# PAPI_M3_RF.net
KiCad netlist of a schematic drawn in Altium Designer
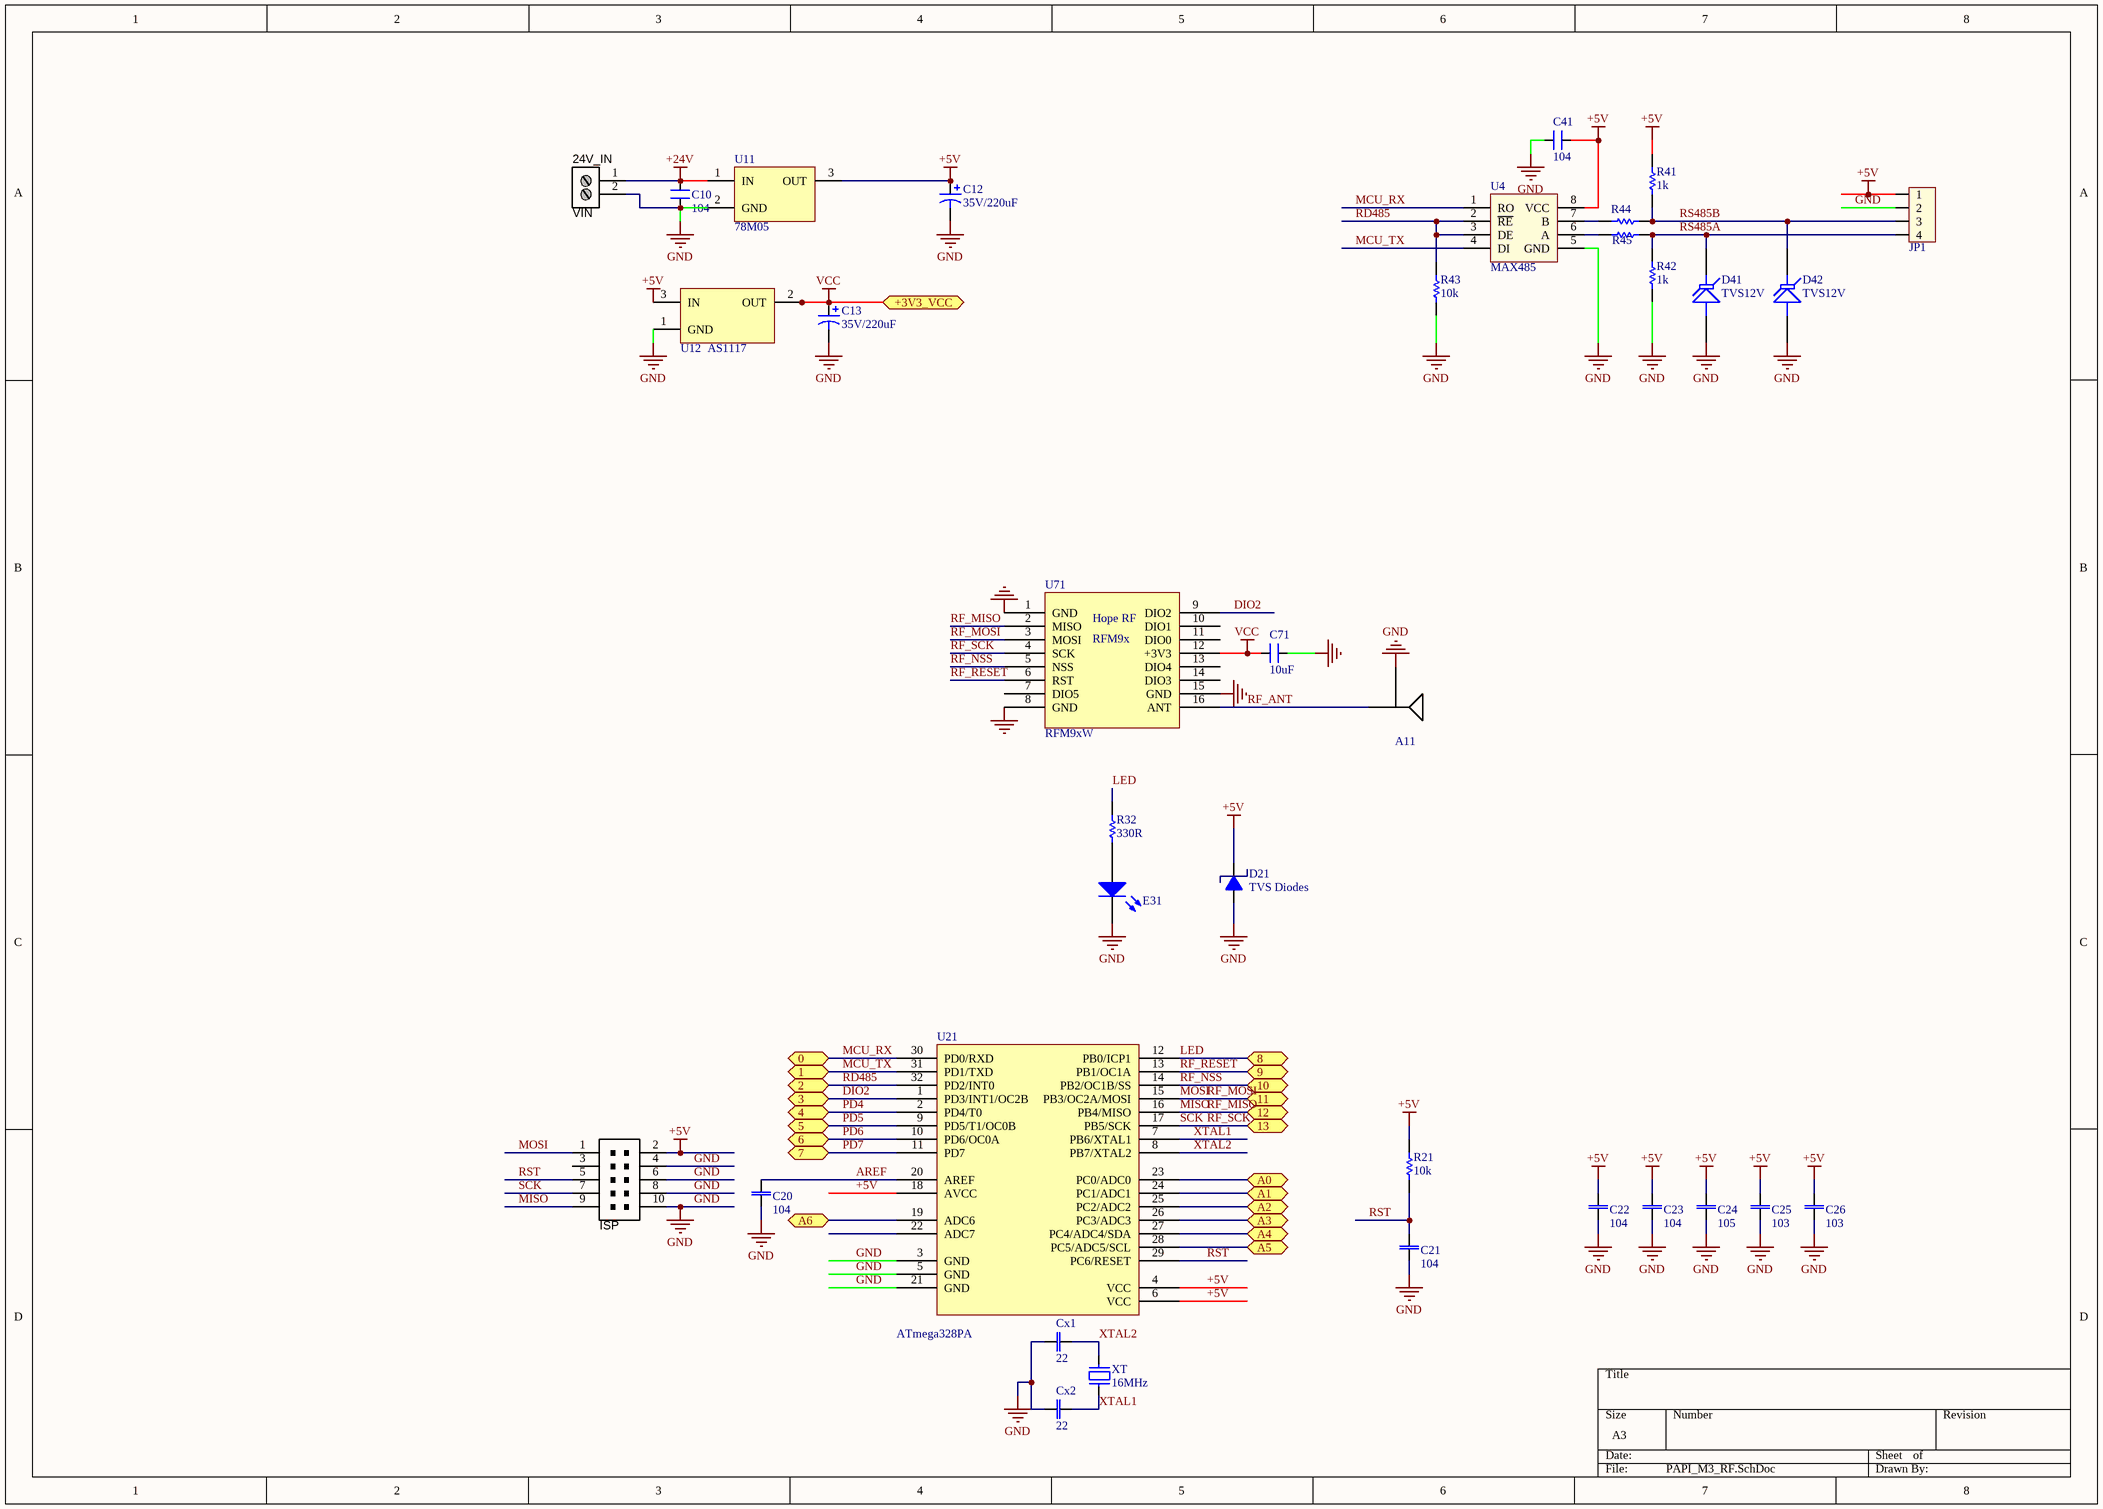
[diagram p0: PAPI_M3_RF.SchDoc]

(export (version "E")
  (design (tool "Eeschema 10.0.6"))
  (components
    (comp (ref "24V_IN")
      (value "VIN")
      (footprint "2P_PCB1")
      (description "Terminal Block Screw Type THT 2-Position 3.81mm pitch")
      (libsource (lib "PBL - Connectors") (part "2P_ScrewTerm_90S_3.81MM"))
    )
    (comp (ref "A11") (value "Giắc anten SMA") (footprint "SMA") (libsource (lib "Tuan") (part "RF_SMA")))
    (comp (ref "C10")
      (value "104")
      (footprint "CAPC2012N_F")
      (fields (field (name "Comment") "Cap_104_0603"))
      (libsource (lib "") (part "CAP NP_1"))
    )
    (comp (ref "C12")
      (value "35V/220uF")
      (footprint "CAPE3.5-5.0MM_Rad_10x14mm")
      (fields (field (name "Comment") "Cap"))
      (libsource (lib "Tuan") (part "Cap"))
    )
    (comp (ref "C13")
      (value "35V/220uF")
      (footprint "CAPE3.5-5.0MM_Rad_10x14mm")
      (fields (field (name "Comment") "Cap"))
      (libsource (lib "Tuan") (part "Cap"))
    )
    (comp (ref "C20")
      (value "104")
      (footprint "PBL - SMD Packages:CAPC2012N_F")
      (description "Capacitor non polarized")
      (fields (field (name "Comment") "Tụ điện dán 0603104"))
      (libsource (lib "Tuan") (part "CAP NP"))
    )
    (comp (ref "C21")
      (value "104")
      (footprint "PBL - SMD Packages:CAPC2012N_F")
      (description "Capacitor non polarized")
      (fields (field (name "Comment") "Tụ điện dán 0603104"))
      (libsource (lib "Tuan") (part "CAP NP"))
    )
    (comp (ref "C22")
      (value "104")
      (footprint "PBL - SMD Packages:CAPC2012N_F")
      (description "Capacitor non polarized")
      (fields (field (name "Comment") "Tụ điện dán 0805104"))
      (libsource (lib "Tuan") (part "CAP NP"))
    )
    (comp (ref "C23")
      (value "104")
      (footprint "PBL - SMD Packages:CAPC2012N_F")
      (description "Capacitor non polarized")
      (fields (field (name "Comment") "Tụ điện dán 0805104"))
      (libsource (lib "Tuan") (part "CAP NP"))
    )
    (comp (ref "C24")
      (value "105")
      (footprint "PBL - SMD Packages:CAPC2012N_F")
      (description "Capacitor non polarized")
      (fields (field (name "Comment") "Tụ điện dán 0805105"))
      (libsource (lib "Tuan") (part "CAP NP"))
    )
    (comp (ref "C25")
      (value "103")
      (footprint "PBL - SMD Packages:CAPC2012N_F")
      (description "Capacitor non polarized")
      (fields (field (name "Comment") "Tụ điện dán 0805103"))
      (libsource (lib "Tuan") (part "CAP NP"))
    )
    (comp (ref "C26")
      (value "103")
      (footprint "PBL - SMD Packages:CAPC2012N_F")
      (description "Capacitor non polarized")
      (fields (field (name "Comment") "Tụ điện dán 0805103"))
      (libsource (lib "Tuan") (part "CAP NP"))
    )
    (comp (ref "C41")
      (value "104")
      (footprint "CAPC2012N_F")
      (fields (field (name "Comment") "Cap_104_0603"))
      (libsource (lib "") (part "CAP NP_1"))
    )
    (comp (ref "C71")
      (value "10uF")
      (footprint "CAPC2012N_F")
      (fields (field (name "Comment") "Cap_10uF_0805"))
      (libsource (lib "") (part "CAP NP_1"))
    )
    (comp (ref "Cx1")
      (value "22")
      (footprint "PBL - SMD Packages:CAPC2012N_F")
      (description "Capacitor non polarized")
      (fields (field (name "Comment") "Tụ điện dán 060322"))
      (libsource (lib "Tuan") (part "CAP NP"))
    )
    (comp (ref "Cx2")
      (value "22")
      (footprint "PBL - SMD Packages:CAPC2012N_F")
      (description "Capacitor non polarized")
      (fields (field (name "Comment") "Tụ điện dán 060322"))
      (libsource (lib "Tuan") (part "CAP NP"))
    )
    (comp (ref "D21")
      (value "TVS Diodes")
      (footprint "DO-214AC")
      (description "TVS Diodes - Transient Voltage Suppressors")
      (libsource (lib "Tuan") (part "TVS Diodes"))
    )
    (comp (ref "D41")
      (value "TVS12V")
      (footprint "DO-214AA")
      (description "Transient Voltage Suppression (TVS) Diode")
      (fields (field (name "PUBLISHER") "Altium Limited"))
      (libsource (lib "Miscellaneous Devices") (part "Tranzorb"))
    )
    (comp (ref "D42")
      (value "TVS12V")
      (footprint "DO-214AA")
      (description "Transient Voltage Suppression (TVS) Diode")
      (fields (field (name "PUBLISHER") "Altium Limited"))
      (libsource (lib "Miscellaneous Devices") (part "Tranzorb"))
    )
    (comp (ref "E31") (value "Led") (footprint "LED 5mm Green") (libsource (lib "Tuan") (part "Led")))
    (comp (ref "ISP")
      (value "Giắc đôi 5x2 chân 2.54mm")
      (footprint "10P_PCB_HEADER_BRD_MNT")
      (description "Header THD 10 POS Double-row 2.54mm pitch")
      (libsource (lib "PBL - Connectors") (part "CONN_HEADER_2x5P_0.100in_Male"))
    )
    (comp (ref "JP1")
      (value "JP4")
      (footprint "heromap:CON4")
      (description "Connector 4")
      (libsource (lib "heromap") (part "Con4"))
    )
    (comp (ref "R21")
      (value "10k")
      (footprint "PBL - SMD Packages:RESC2012N_F")
      (description "Resistor")
      (fields (field (name "Comment") "Điện trở dán 060310k"))
      (libsource (lib "Tuan") (part "Res"))
    )
    (comp (ref "R32")
      (value "330R")
      (footprint "PBL - SMD Packages:RESC2012N_F")
      (description "Resistor")
      (fields (field (name "Comment") "Điện trở dán 0603330R"))
      (libsource (lib "Tuan") (part "Res"))
    )
    (comp (ref "R41")
      (value "1k")
      (footprint "RESC2012N_F")
      (fields (field (name "Comment") "Res_1k_0603"))
      (libsource (lib "Tuan") (part "Res"))
    )
    (comp (ref "R42")
      (value "1k")
      (footprint "RESC2012N_F")
      (fields (field (name "Comment") "Res_1k_0603"))
      (libsource (lib "Tuan") (part "Res"))
    )
    (comp (ref "R43")
      (value "10k")
      (footprint "RESC2012N_F")
      (fields (field (name "Comment") "Res_10k_0603"))
      (libsource (lib "Tuan") (part "Res"))
    )
    (comp (ref "R44") (value "Res_10R_0805") (footprint "RESC2012N_F") (libsource (lib "Tuan") (part "Res")))
    (comp (ref "R45") (value "Res_10R_0805") (footprint "RESC2012N_F") (libsource (lib "Tuan") (part "Res")))
    (comp (ref "U4")
      (value "MAX485")
      (footprint "SOIC 8")
      (description "RS232 - RS485 (Same sn75176)")
      (libsource (lib "heromap") (part "MAX485"))
    )
    (comp (ref "U11") (value "78M05") (footprint "TO252 D-PAK") (libsource (lib "Tuan") (part "LM78xx")))
    (comp (ref "U12") (value "AS1117") (footprint "SOT223-4N") (libsource (lib "Tuan") (part "AS1117")))
    (comp (ref "U21")
      (value "ATmega328PA")
      (footprint "TQFP32")
      (description "ATmega48/168/328")
      (libsource (lib "Tuan") (part "ATmega48/168/328"))
    )
    (comp (ref "U71") (value "RFM9xW") (footprint "RFM9xW") (libsource (lib "Tuan") (part "RFM9xW")))
    (comp (ref "XT") (value "16MHz") (footprint "XT2") (libsource (lib "Tuan") (part "Crystal")))
  )
  (nets
    (net (code "1") (name "+5V") (class "Default")
      (node (ref "C12") (pin "1") (pinfunction "1_1") (pintype "passive"))
      (node (ref "C22") (pin "2") (pinfunction "2_2") (pintype "passive"))
      (node (ref "C23") (pin "2") (pinfunction "2_2") (pintype "passive"))
      (node (ref "C24") (pin "2") (pinfunction "2_2") (pintype "passive"))
      (node (ref "C25") (pin "2") (pinfunction "2_2") (pintype "passive"))
      (node (ref "C26") (pin "2") (pinfunction "2_2") (pintype "passive"))
      (node (ref "C41") (pin "1") (pinfunction "1_1") (pintype "passive"))
      (node (ref "D21") (pin "K") (pinfunction "K_K") (pintype "passive"))
      (node (ref "ISP") (pin "2") (pinfunction "2_2") (pintype "passive"))
      (node (ref "JP1") (pin "1") (pinfunction "1_1") (pintype "passive"))
      (node (ref "R21") (pin "2") (pinfunction "2_2") (pintype "passive"))
      (node (ref "R41") (pin "2") (pinfunction "2_2") (pintype "passive"))
      (node (ref "U11") (pin "3") (pinfunction "OUT_3") (pintype "passive"))
      (node (ref "U12") (pin "3") (pinfunction "IN_3") (pintype "power_in"))
      (node (ref "U21") (pin "18") (pinfunction "AVCC_18") (pintype "passive"))
      (node (ref "U21") (pin "4") (pinfunction "VCC_4") (pintype "passive"))
      (node (ref "U21") (pin "6") (pinfunction "VCC_6") (pintype "passive"))
      (node (ref "U4") (pin "8") (pinfunction "VCC_8") (pintype "passive"))
    )
    (net (code "2") (name "+24V") (class "Default")
      (node (ref "24V_IN") (pin "1") (pinfunction "1_1") (pintype "passive"))
      (node (ref "C10") (pin "2") (pinfunction "2_2") (pintype "passive"))
      (node (ref "U11") (pin "1") (pinfunction "IN_1") (pintype "passive"))
    )
    (net (code "3") (name "/A0") (class "Default")
      (node (ref "U21") (pin "23") (pinfunction "PC0/ADC0_23") (pintype "passive"))
    )
    (net (code "4") (name "/A1") (class "Default")
      (node (ref "U21") (pin "24") (pinfunction "PC1/ADC1_24") (pintype "passive"))
    )
    (net (code "5") (name "/A2") (class "Default")
      (node (ref "U21") (pin "25") (pinfunction "PC2/ADC2_25") (pintype "passive"))
    )
    (net (code "6") (name "/A3") (class "Default")
      (node (ref "U21") (pin "26") (pinfunction "PC3/ADC3_26") (pintype "passive"))
    )
    (net (code "7") (name "/A4") (class "Default")
      (node (ref "U21") (pin "27") (pinfunction "PC4/ADC4/SDA_27") (pintype "passive"))
    )
    (net (code "8") (name "/A5") (class "Default")
      (node (ref "U21") (pin "28") (pinfunction "PC5/ADC5/SCL_28") (pintype "passive"))
    )
    (net (code "9") (name "/A6") (class "Default")
      (node (ref "U21") (pin "19") (pinfunction "ADC6_19") (pintype "passive"))
    )
    (net (code "10") (name "/AREF") (class "Default")
      (node (ref "C20") (pin "2") (pinfunction "2_2") (pintype "passive"))
      (node (ref "U21") (pin "20") (pinfunction "AREF_20") (pintype "passive"))
    )
    (net (code "11") (name "/DIO2") (class "Default")
      (node (ref "U21") (pin "1") (pinfunction "PD3/INT1/OC2B_1") (pintype "passive"))
      (node (ref "U71") (pin "9") (pinfunction "DIO2_9") (pintype "passive"))
    )
    (net (code "12") (name "/LED") (class "Default")
      (node (ref "R32") (pin "1") (pinfunction "1_1") (pintype "passive"))
      (node (ref "U21") (pin "12") (pinfunction "PB0/ICP1_12") (pintype "passive"))
    )
    (net (code "13") (name "/MCU_RX") (class "Default")
      (node (ref "U21") (pin "30") (pinfunction "PD0/RXD_30") (pintype "passive"))
      (node (ref "U4") (pin "1") (pinfunction "RO_1") (pintype "passive"))
    )
    (net (code "14") (name "/MCU_TX") (class "Default")
      (node (ref "U21") (pin "31") (pinfunction "PD1/TXD_31") (pintype "passive"))
      (node (ref "U4") (pin "4") (pinfunction "DI_4") (pintype "passive"))
    )
    (net (code "15") (name "/MISO") (class "Default")
      (node (ref "ISP") (pin "9") (pinfunction "9_9") (pintype "passive"))
      (node (ref "U21") (pin "16") (pinfunction "PB4/MISO_16") (pintype "passive"))
      (node (ref "U71") (pin "2") (pinfunction "MISO_2") (pintype "passive"))
    )
    (net (code "16") (name "/MOSI") (class "Default")
      (node (ref "ISP") (pin "1") (pinfunction "1_1") (pintype "passive"))
      (node (ref "U21") (pin "15") (pinfunction "PB3/OC2A/MOSI_15") (pintype "passive"))
      (node (ref "U71") (pin "3") (pinfunction "MOSI_3") (pintype "passive"))
    )
    (net (code "17") (name "/PD4") (class "Default")
      (node (ref "U21") (pin "2") (pinfunction "PD4/T0_2") (pintype "passive"))
    )
    (net (code "18") (name "/PD5") (class "Default")
      (node (ref "U21") (pin "9") (pinfunction "PD5/T1/OC0B_9") (pintype "passive"))
    )
    (net (code "19") (name "/PD6") (class "Default")
      (node (ref "U21") (pin "10") (pinfunction "PD6/OC0A_10") (pintype "passive"))
    )
    (net (code "20") (name "/PD7") (class "Default")
      (node (ref "U21") (pin "11") (pinfunction "PD7_11") (pintype "passive"))
    )
    (net (code "21") (name "/RD485") (class "Default")
      (node (ref "R43") (pin "2") (pinfunction "2_2") (pintype "passive"))
      (node (ref "U21") (pin "32") (pinfunction "PD2/INT0_32") (pintype "passive"))
      (node (ref "U4") (pin "2") (pinfunction "~{RE}_2") (pintype "passive"))
      (node (ref "U4") (pin "3") (pinfunction "DE_3") (pintype "passive"))
    )
    (net (code "22") (name "/RF_ANT") (class "Default")
      (node (ref "A11") (pin "1") (pinfunction "RF_1") (pintype "passive"))
      (node (ref "U71") (pin "16") (pinfunction "ANT_16") (pintype "passive"))
    )
    (net (code "23") (name "/RF_NSS") (class "Default")
      (node (ref "U21") (pin "14") (pinfunction "PB2/OC1B/SS_14") (pintype "passive"))
      (node (ref "U71") (pin "5") (pinfunction "NSS_5") (pintype "passive"))
    )
    (net (code "24") (name "/RF_RESET") (class "Default")
      (node (ref "U21") (pin "13") (pinfunction "PB1/OC1A_13") (pintype "passive"))
      (node (ref "U71") (pin "6") (pinfunction "RST_6") (pintype "passive"))
    )
    (net (code "25") (name "/RF_SCK") (class "Default")
      (node (ref "ISP") (pin "7") (pinfunction "7_7") (pintype "passive"))
      (node (ref "U21") (pin "17") (pinfunction "PB5/SCK_17") (pintype "passive"))
      (node (ref "U71") (pin "4") (pinfunction "SCK_4") (pintype "passive"))
    )
    (net (code "26") (name "/RS485A") (class "Default")
      (node (ref "D41") (pin "2") (pinfunction "K_2") (pintype "passive"))
      (node (ref "JP1") (pin "4") (pinfunction "4_4") (pintype "passive"))
      (node (ref "R42") (pin "2") (pinfunction "2_2") (pintype "passive"))
      (node (ref "R45") (pin "2") (pinfunction "2_2") (pintype "passive"))
    )
    (net (code "27") (name "/RS485B") (class "Default")
      (node (ref "D42") (pin "2") (pinfunction "K_2") (pintype "passive"))
      (node (ref "JP1") (pin "3") (pinfunction "3_3") (pintype "passive"))
      (node (ref "R41") (pin "1") (pinfunction "1_1") (pintype "passive"))
      (node (ref "R44") (pin "2") (pinfunction "2_2") (pintype "passive"))
    )
    (net (code "28") (name "/RST") (class "Default")
      (node (ref "C21") (pin "2") (pinfunction "2_2") (pintype "passive"))
      (node (ref "ISP") (pin "5") (pinfunction "5_5") (pintype "passive"))
      (node (ref "R21") (pin "1") (pinfunction "1_1") (pintype "passive"))
      (node (ref "U21") (pin "29") (pinfunction "PC6/RESET_29") (pintype "passive"))
    )
    (net (code "29") (name "/XTAL1") (class "Default")
      (node (ref "Cx2") (pin "1") (pinfunction "1_1") (pintype "passive"))
      (node (ref "U21") (pin "7") (pinfunction "PB6/XTAL1_7") (pintype "passive"))
      (node (ref "XT") (pin "1") (pinfunction "1_1") (pintype "passive"))
    )
    (net (code "30") (name "/XTAL2") (class "Default")
      (node (ref "Cx1") (pin "1") (pinfunction "1_1") (pintype "passive"))
      (node (ref "U21") (pin "8") (pinfunction "PB7/XTAL2_8") (pintype "passive"))
      (node (ref "XT") (pin "2") (pinfunction "2_2") (pintype "passive"))
    )
    (net (code "31") (name "GND") (class "Default")
      (node (ref "24V_IN") (pin "2") (pinfunction "2_2") (pintype "passive"))
      (node (ref "A11") (pin "2") (pinfunction "G_2") (pintype "passive"))
      (node (ref "C10") (pin "1") (pinfunction "1_1") (pintype "passive"))
      (node (ref "C12") (pin "2") (pinfunction "2_2") (pintype "passive"))
      (node (ref "C13") (pin "2") (pinfunction "2_2") (pintype "passive"))
      (node (ref "C20") (pin "1") (pinfunction "1_1") (pintype "passive"))
      (node (ref "C21") (pin "1") (pinfunction "1_1") (pintype "passive"))
      (node (ref "C22") (pin "1") (pinfunction "1_1") (pintype "passive"))
      (node (ref "C23") (pin "1") (pinfunction "1_1") (pintype "passive"))
      (node (ref "C24") (pin "1") (pinfunction "1_1") (pintype "passive"))
      (node (ref "C25") (pin "1") (pinfunction "1_1") (pintype "passive"))
      (node (ref "C26") (pin "1") (pinfunction "1_1") (pintype "passive"))
      (node (ref "C41") (pin "2") (pinfunction "2_2") (pintype "passive"))
      (node (ref "C71") (pin "1") (pinfunction "1_1") (pintype "passive"))
      (node (ref "Cx1") (pin "2") (pinfunction "2_2") (pintype "passive"))
      (node (ref "Cx2") (pin "2") (pinfunction "2_2") (pintype "passive"))
      (node (ref "D21") (pin "A") (pinfunction "A_A") (pintype "passive"))
      (node (ref "D41") (pin "1") (pinfunction "A_1") (pintype "passive"))
      (node (ref "D42") (pin "1") (pinfunction "A_1") (pintype "passive"))
      (node (ref "E31") (pin "2") (pinfunction "K_2") (pintype "passive"))
      (node (ref "ISP") (pin "10") (pinfunction "10_10") (pintype "passive"))
      (node (ref "ISP") (pin "4") (pinfunction "4_4") (pintype "passive"))
      (node (ref "ISP") (pin "6") (pinfunction "6_6") (pintype "passive"))
      (node (ref "ISP") (pin "8") (pinfunction "8_8") (pintype "passive"))
      (node (ref "JP1") (pin "2") (pinfunction "2_2") (pintype "passive"))
      (node (ref "R42") (pin "1") (pinfunction "1_1") (pintype "passive"))
      (node (ref "R43") (pin "1") (pinfunction "1_1") (pintype "passive"))
      (node (ref "U11") (pin "2") (pinfunction "GND_2") (pintype "passive"))
      (node (ref "U12") (pin "1") (pinfunction "GND_1") (pintype "power_in"))
      (node (ref "U21") (pin "21") (pinfunction "GND_21") (pintype "power_in"))
      (node (ref "U21") (pin "3") (pinfunction "GND_3") (pintype "power_in"))
      (node (ref "U21") (pin "5") (pinfunction "GND_5") (pintype "power_in"))
      (node (ref "U4") (pin "5") (pinfunction "GND_5") (pintype "passive"))
      (node (ref "U71") (pin "1") (pinfunction "GND_1") (pintype "passive"))
      (node (ref "U71") (pin "15") (pinfunction "GND_15") (pintype "passive"))
      (node (ref "U71") (pin "8") (pinfunction "GND_8") (pintype "passive"))
    )
    (net (code "32") (name "Net-(E31-A)") (class "Default")
      (node (ref "E31") (pin "1") (pinfunction "A_1") (pintype "passive"))
      (node (ref "R32") (pin "2") (pinfunction "2_2") (pintype "passive"))
    )
    (net (code "33") (name "Net-(U4-A)") (class "Default")
      (node (ref "R45") (pin "1") (pinfunction "1_1") (pintype "passive"))
      (node (ref "U4") (pin "6") (pinfunction "A_6") (pintype "passive"))
    )
    (net (code "34") (name "Net-(U4-B)") (class "Default")
      (node (ref "R44") (pin "1") (pinfunction "1_1") (pintype "passive"))
      (node (ref "U4") (pin "7") (pinfunction "B_7") (pintype "passive"))
    )
    (net (code "35") (name "VCC") (class "Default")
      (node (ref "C13") (pin "1") (pinfunction "1_1") (pintype "passive"))
      (node (ref "C71") (pin "2") (pinfunction "2_2") (pintype "passive"))
      (node (ref "U12") (pin "2") (pinfunction "OUT_2") (pintype "power_in"))
      (node (ref "U12") (pin "4") (pinfunction "4_4") (pintype "passive"))
      (node (ref "U71") (pin "12") (pinfunction "+3V3_12") (pintype "passive"))
    )
    (net (code "36") (name "unconnected-(ISP-Pad3)") (class "Default")
      (node (ref "ISP") (pin "3") (pinfunction "3_3") (pintype "passive"))
    )
    (net (code "37") (name "unconnected-(U21-ADC7-Pad22)") (class "Default")
      (node (ref "U21") (pin "22") (pinfunction "ADC7_22") (pintype "passive"))
    )
    (net (code "38") (name "unconnected-(U71-DIO0-Pad11)") (class "Default")
      (node (ref "U71") (pin "11") (pinfunction "DIO0_11") (pintype "passive"))
    )
    (net (code "39") (name "unconnected-(U71-DIO1-Pad10)") (class "Default")
      (node (ref "U71") (pin "10") (pinfunction "DIO1_10") (pintype "passive"))
    )
    (net (code "40") (name "unconnected-(U71-DIO3-Pad14)") (class "Default")
      (node (ref "U71") (pin "14") (pinfunction "DIO3_14") (pintype "passive"))
    )
    (net (code "41") (name "unconnected-(U71-DIO4-Pad13)") (class "Default")
      (node (ref "U71") (pin "13") (pinfunction "DIO4_13") (pintype "passive"))
    )
    (net (code "42") (name "unconnected-(U71-DIO5-Pad7)") (class "Default")
      (node (ref "U71") (pin "7") (pinfunction "DIO5_7") (pintype "passive"))
    )
  )
)
